# msq_ethrottle_soic.net
KiCad netlist of a schematic drawn in EasyEDA Pro
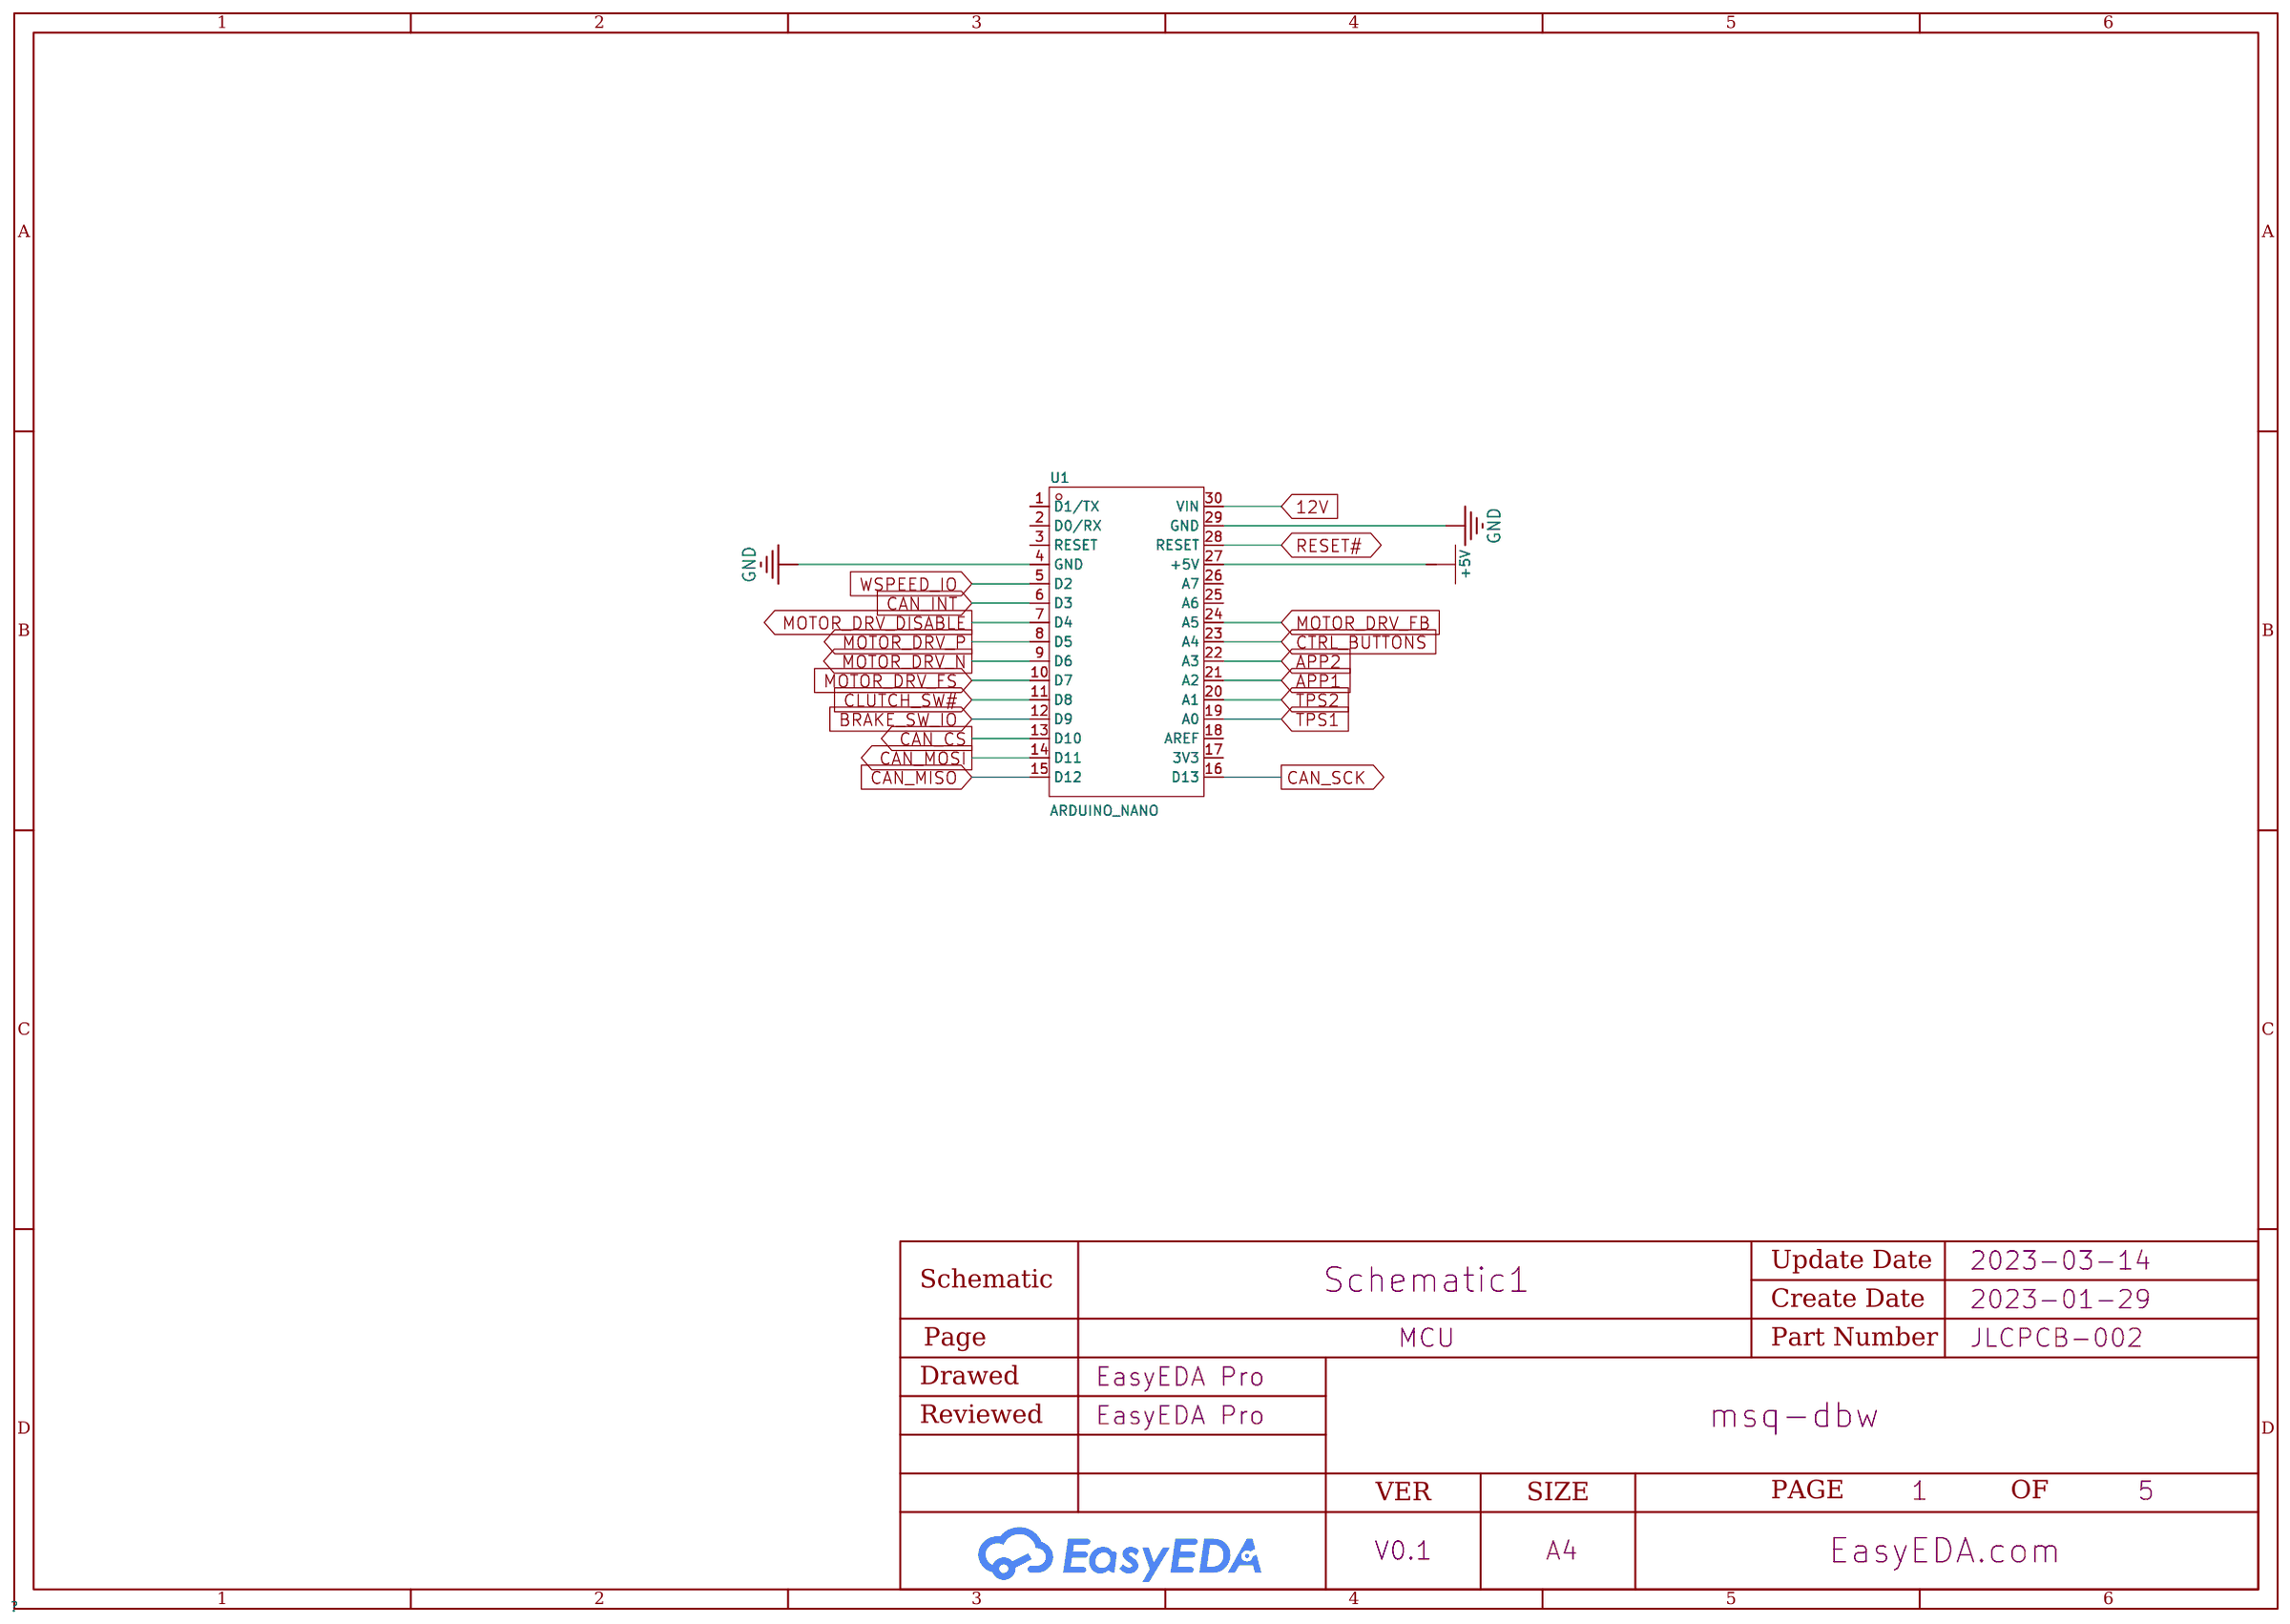
[diagram p0: MCU]
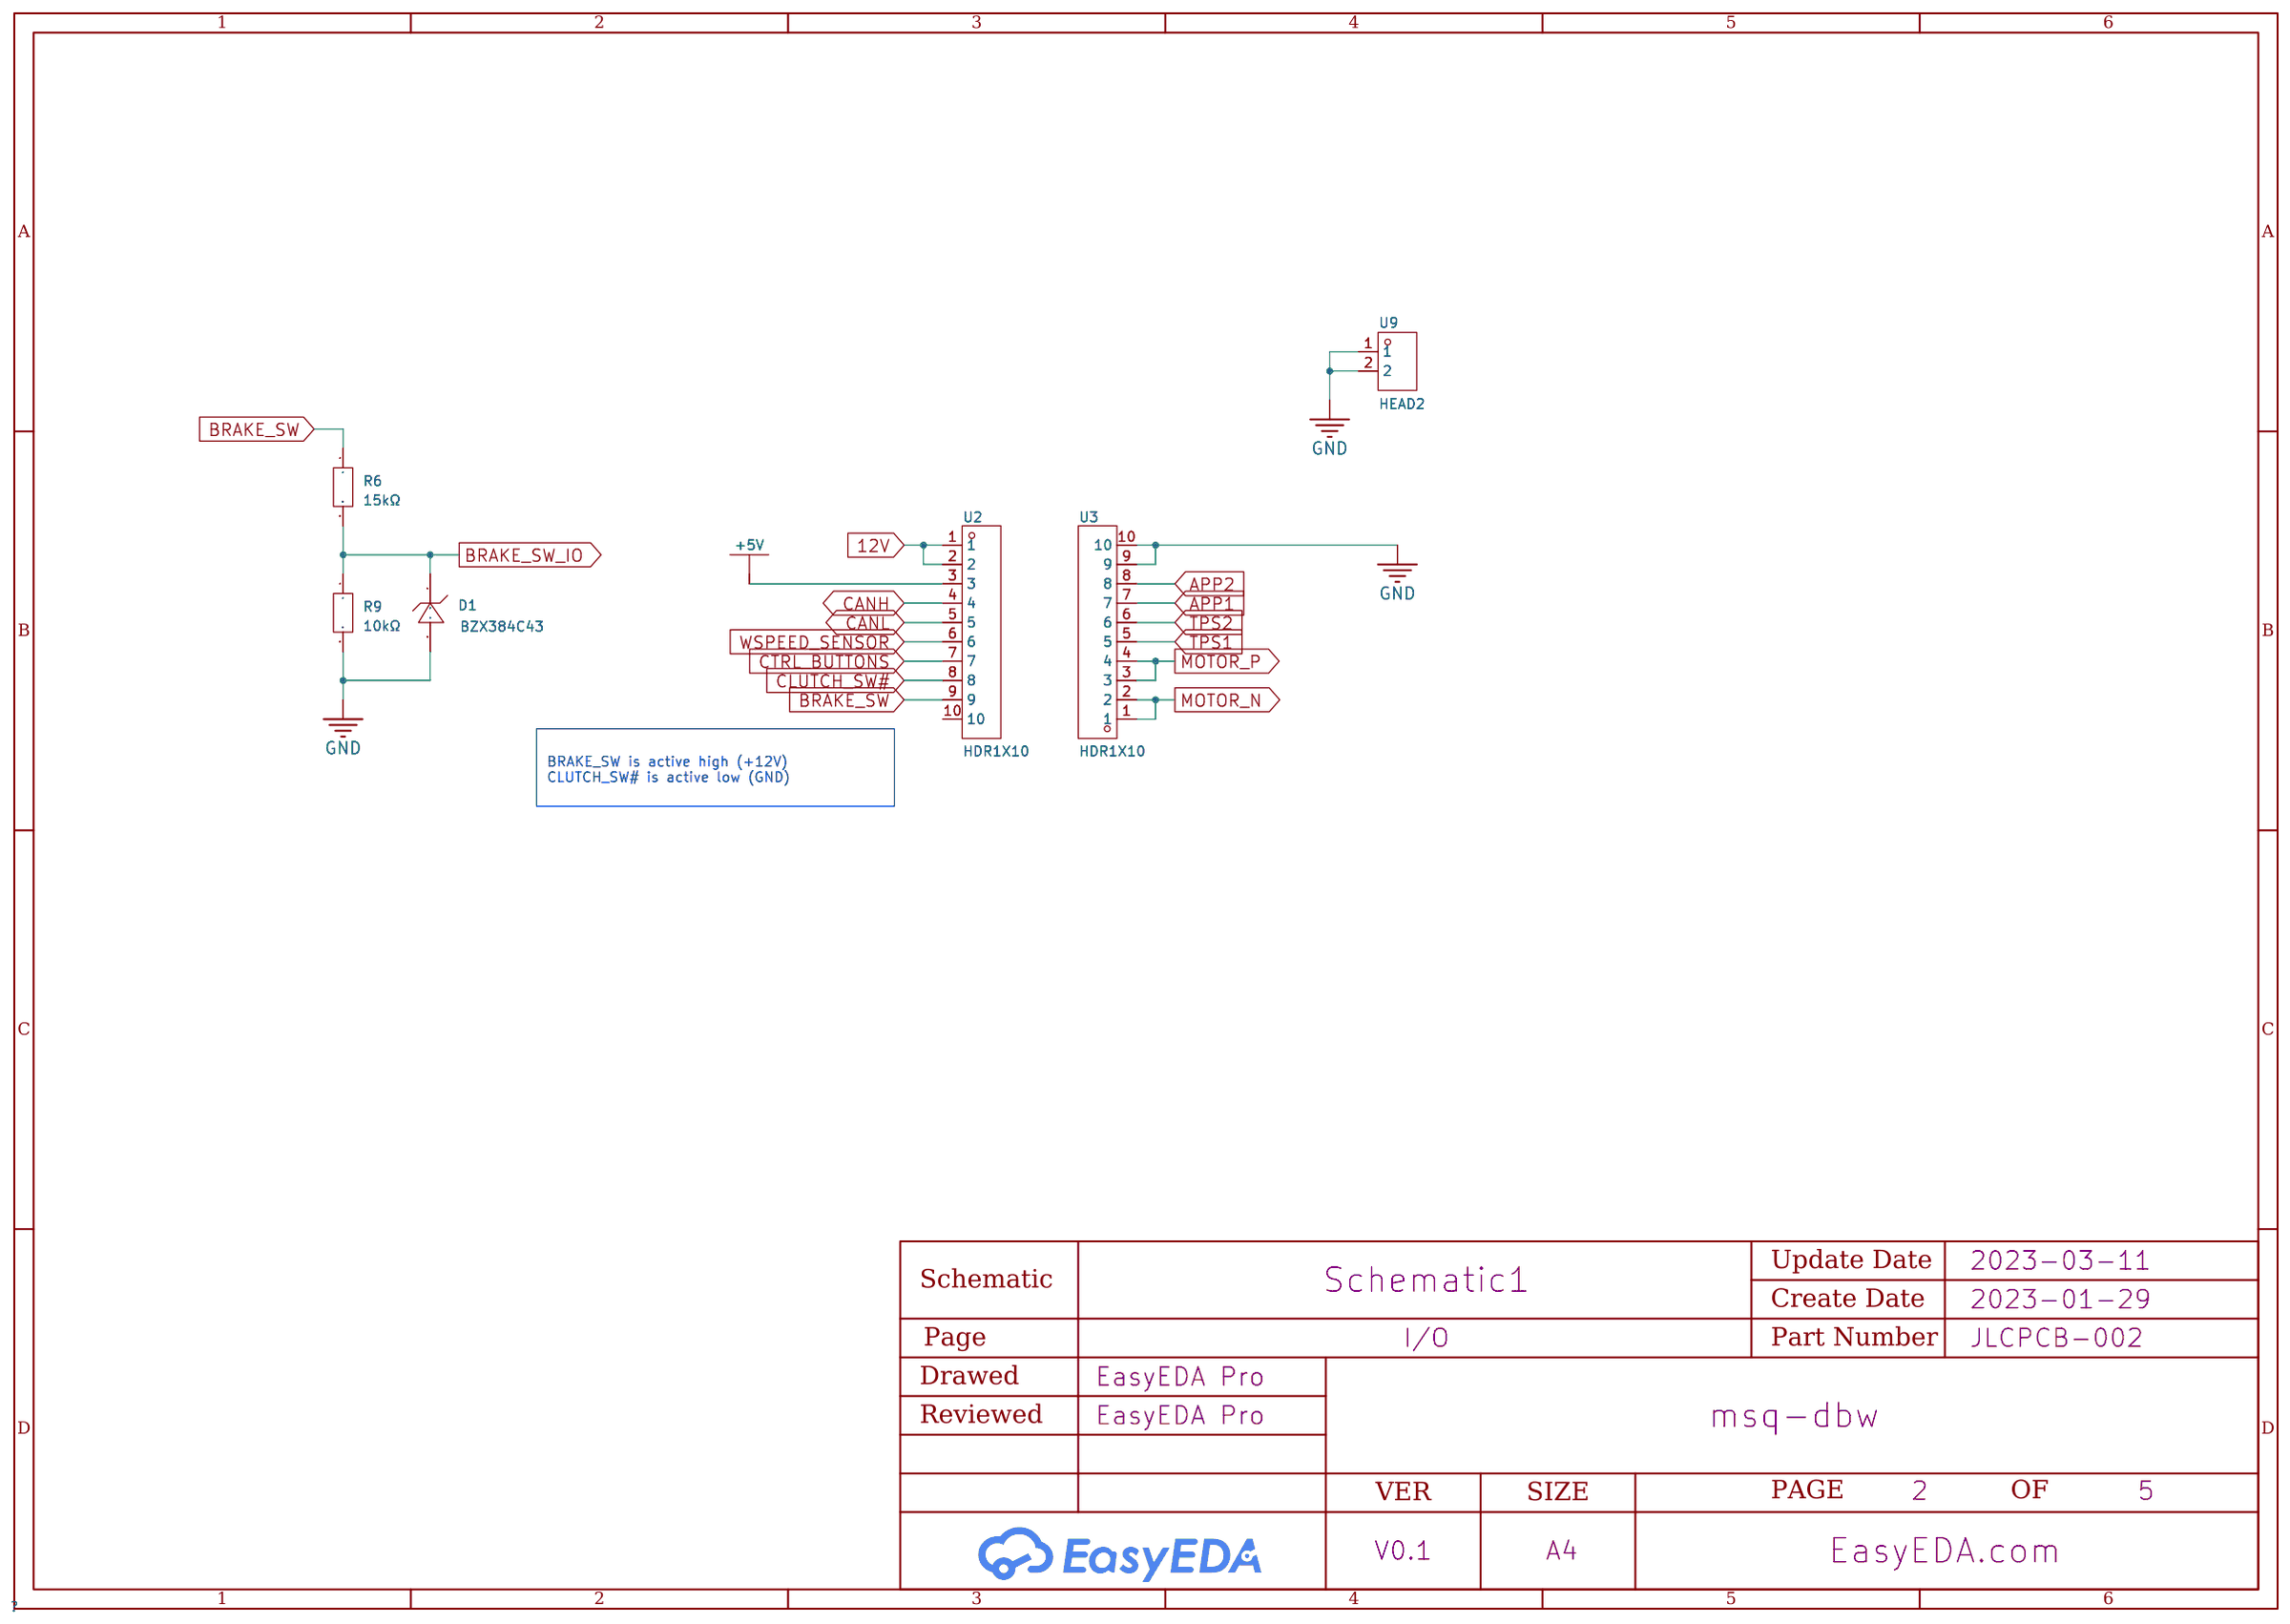
[diagram p1: I/O]
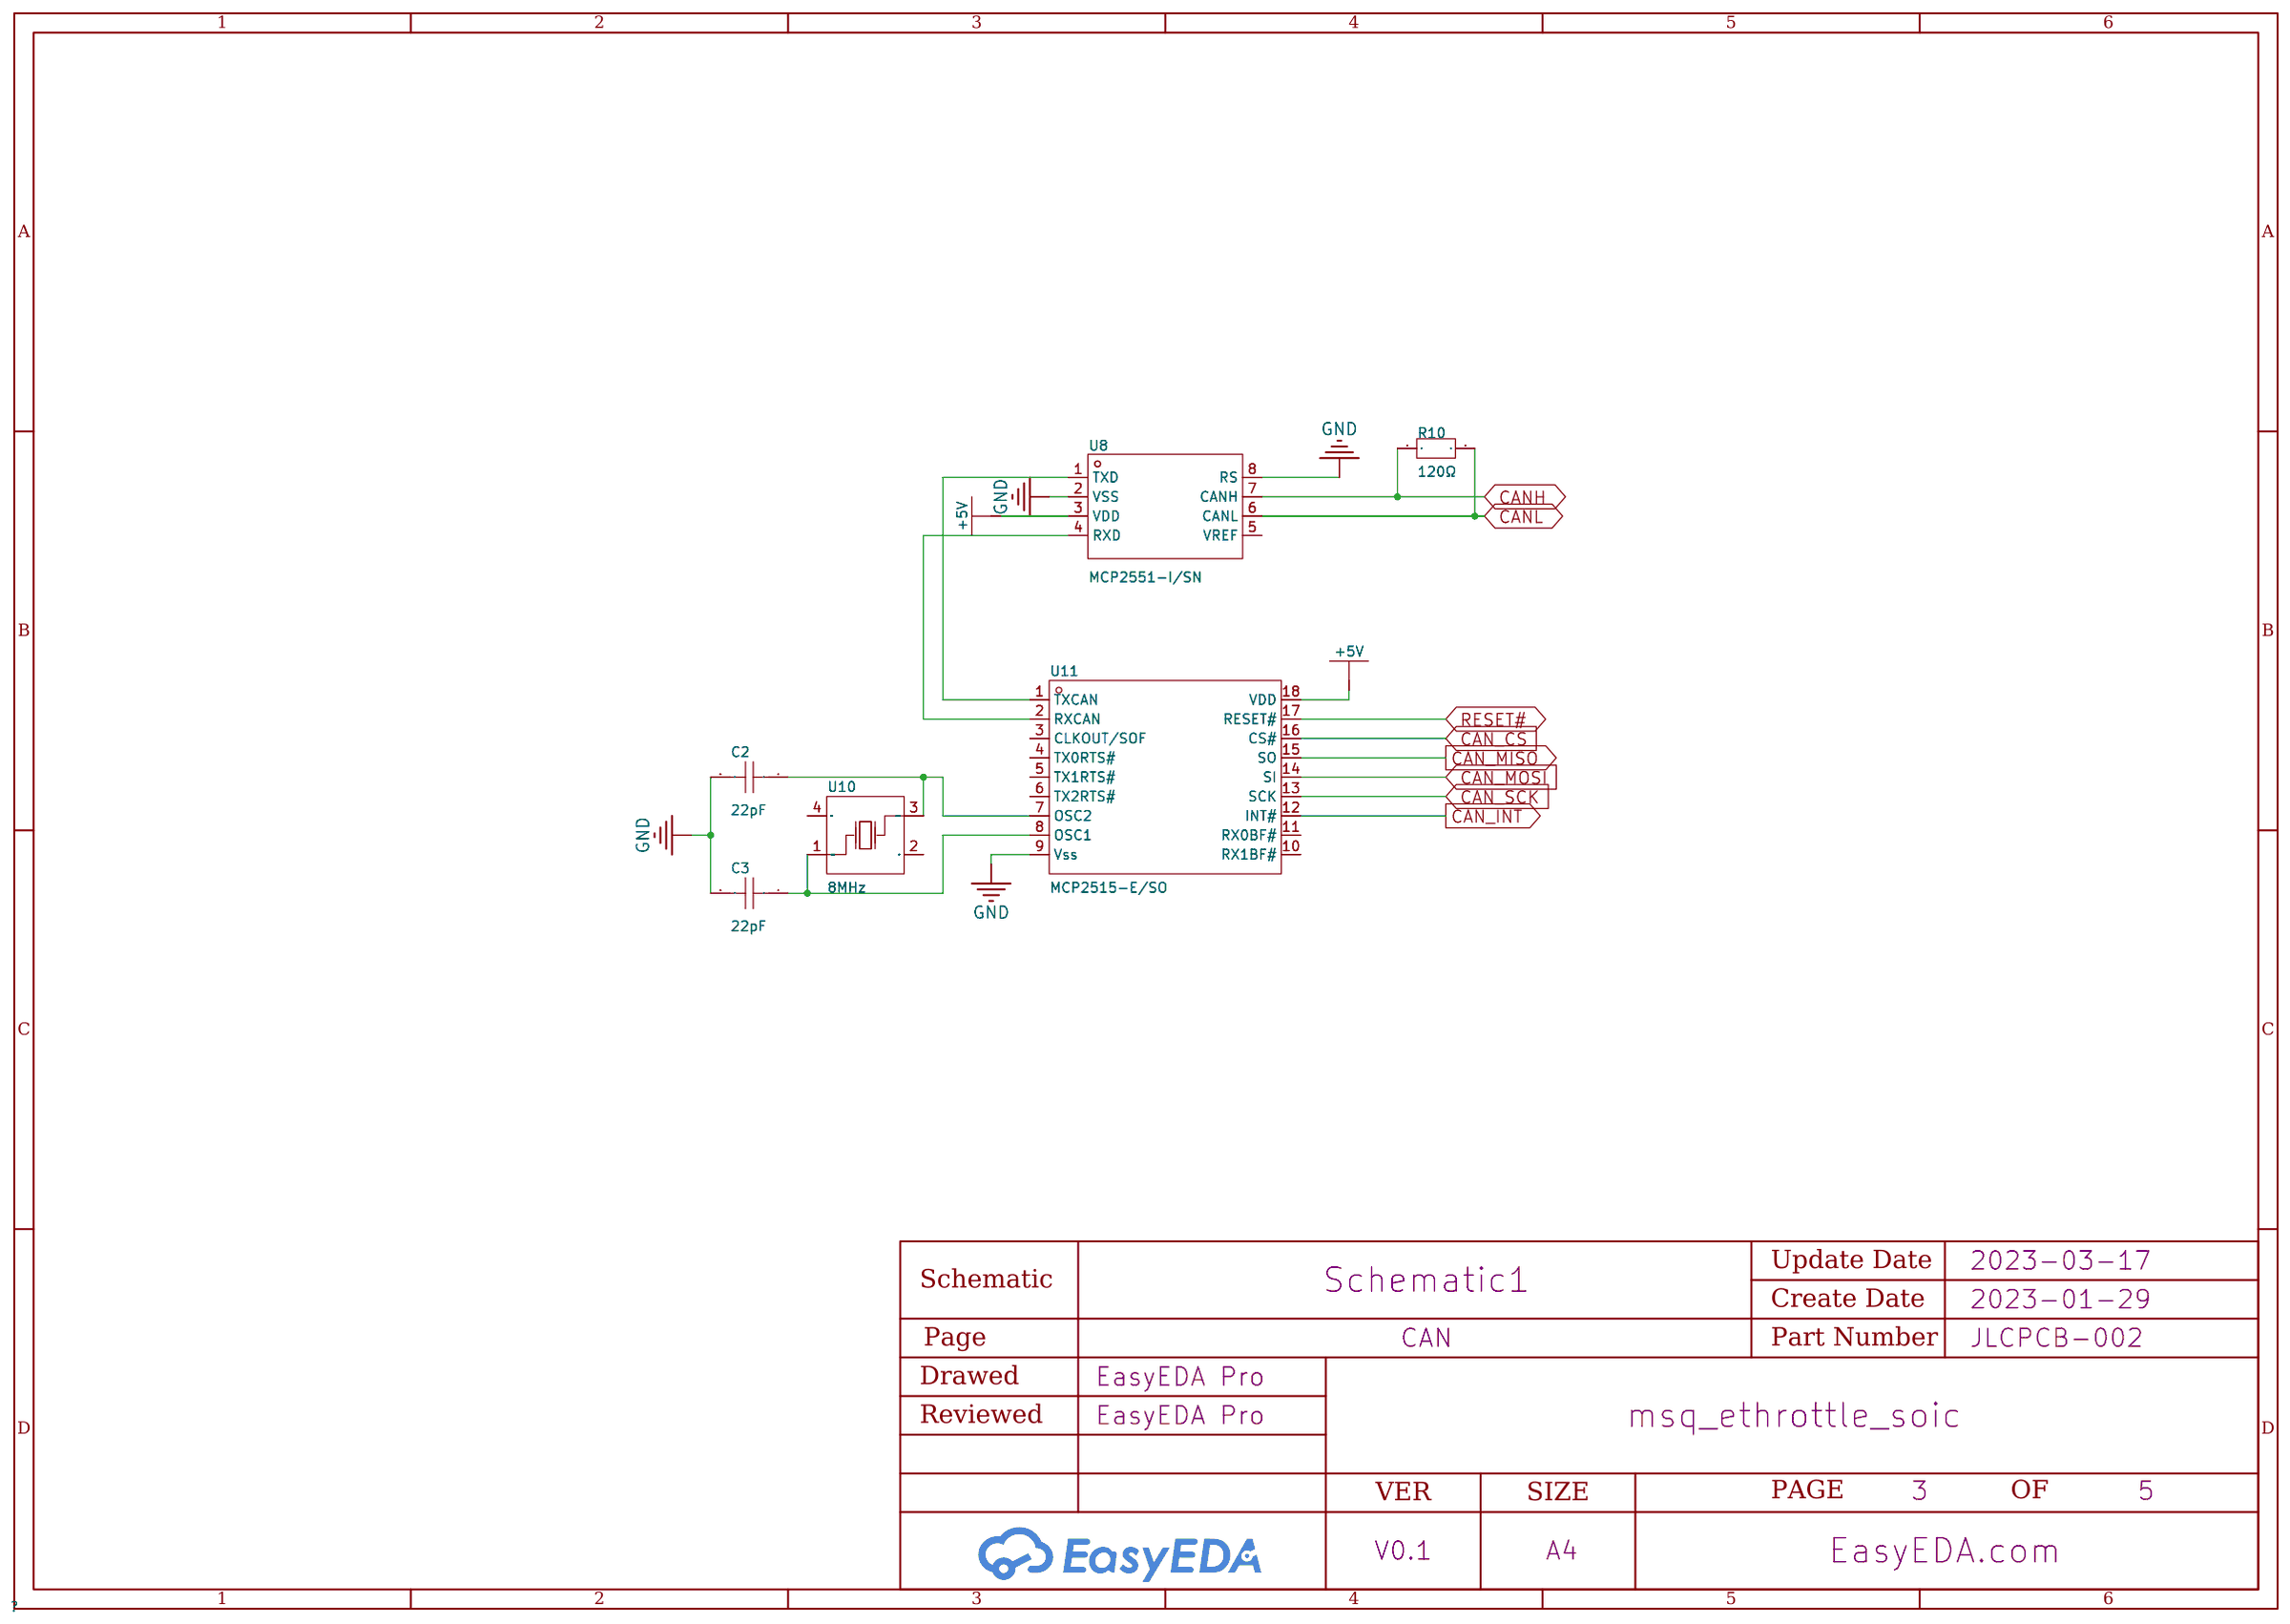
[diagram p2: CAN]
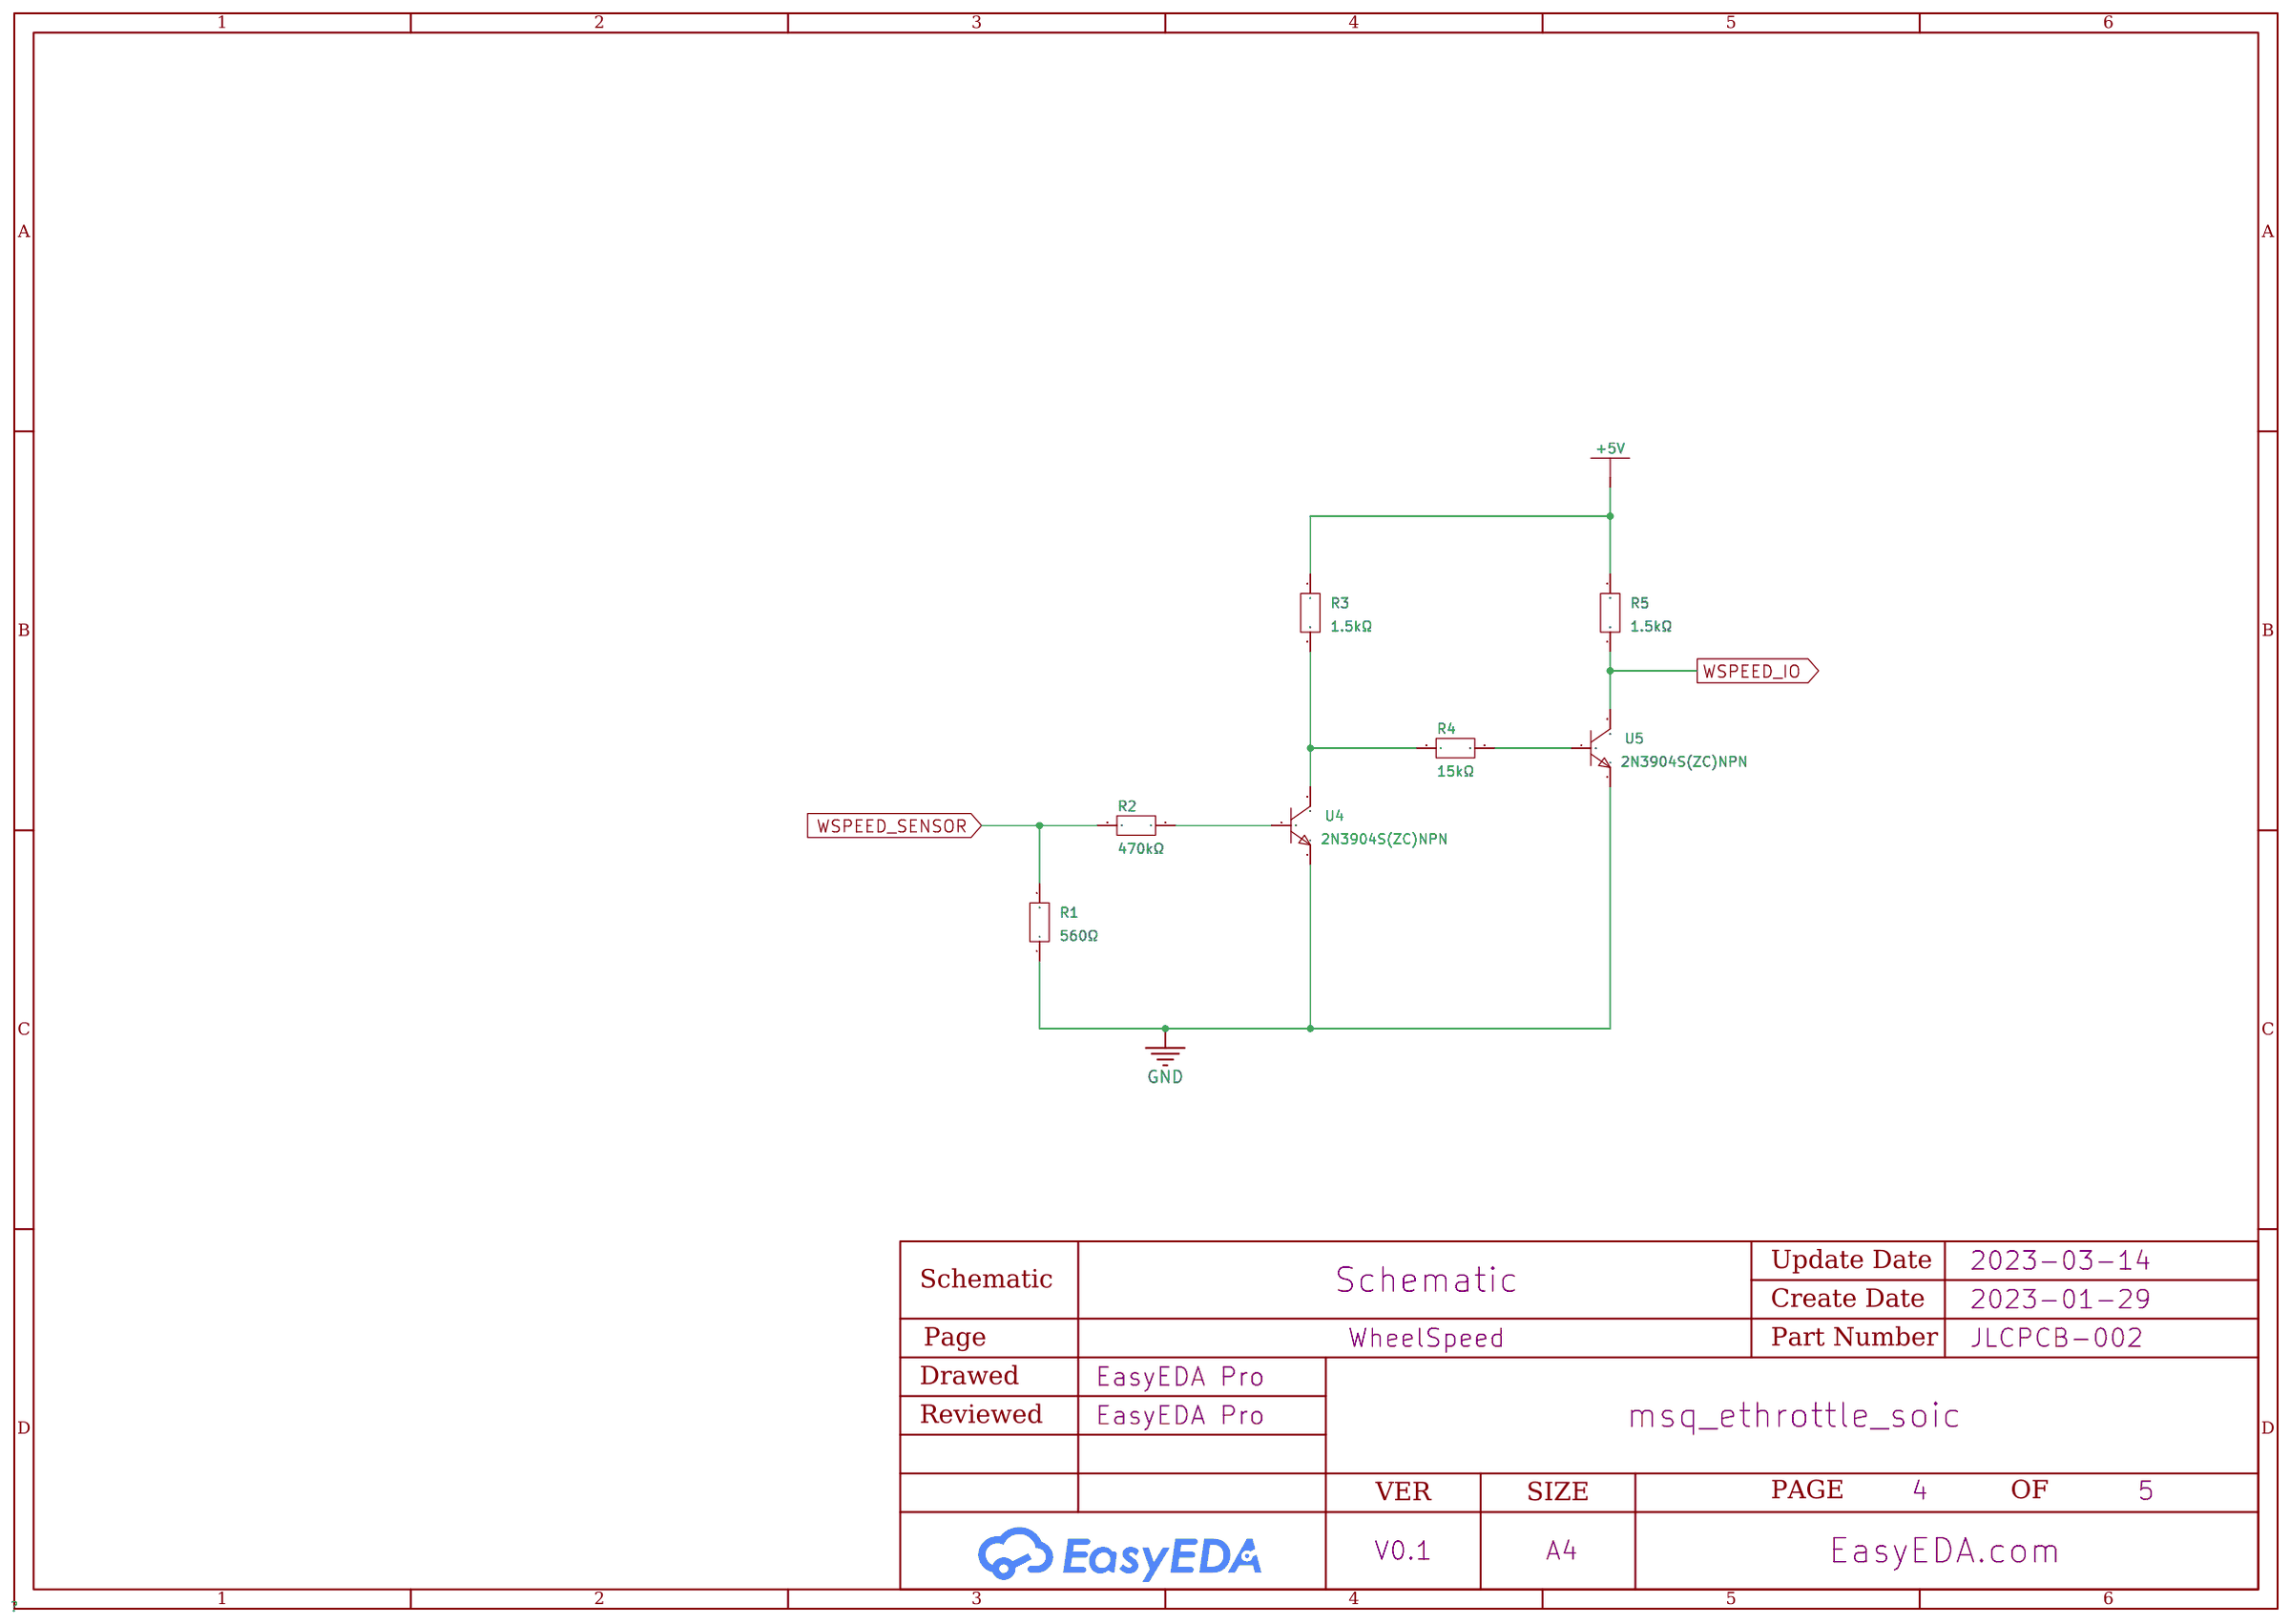
[diagram p3: WheelSpeed]
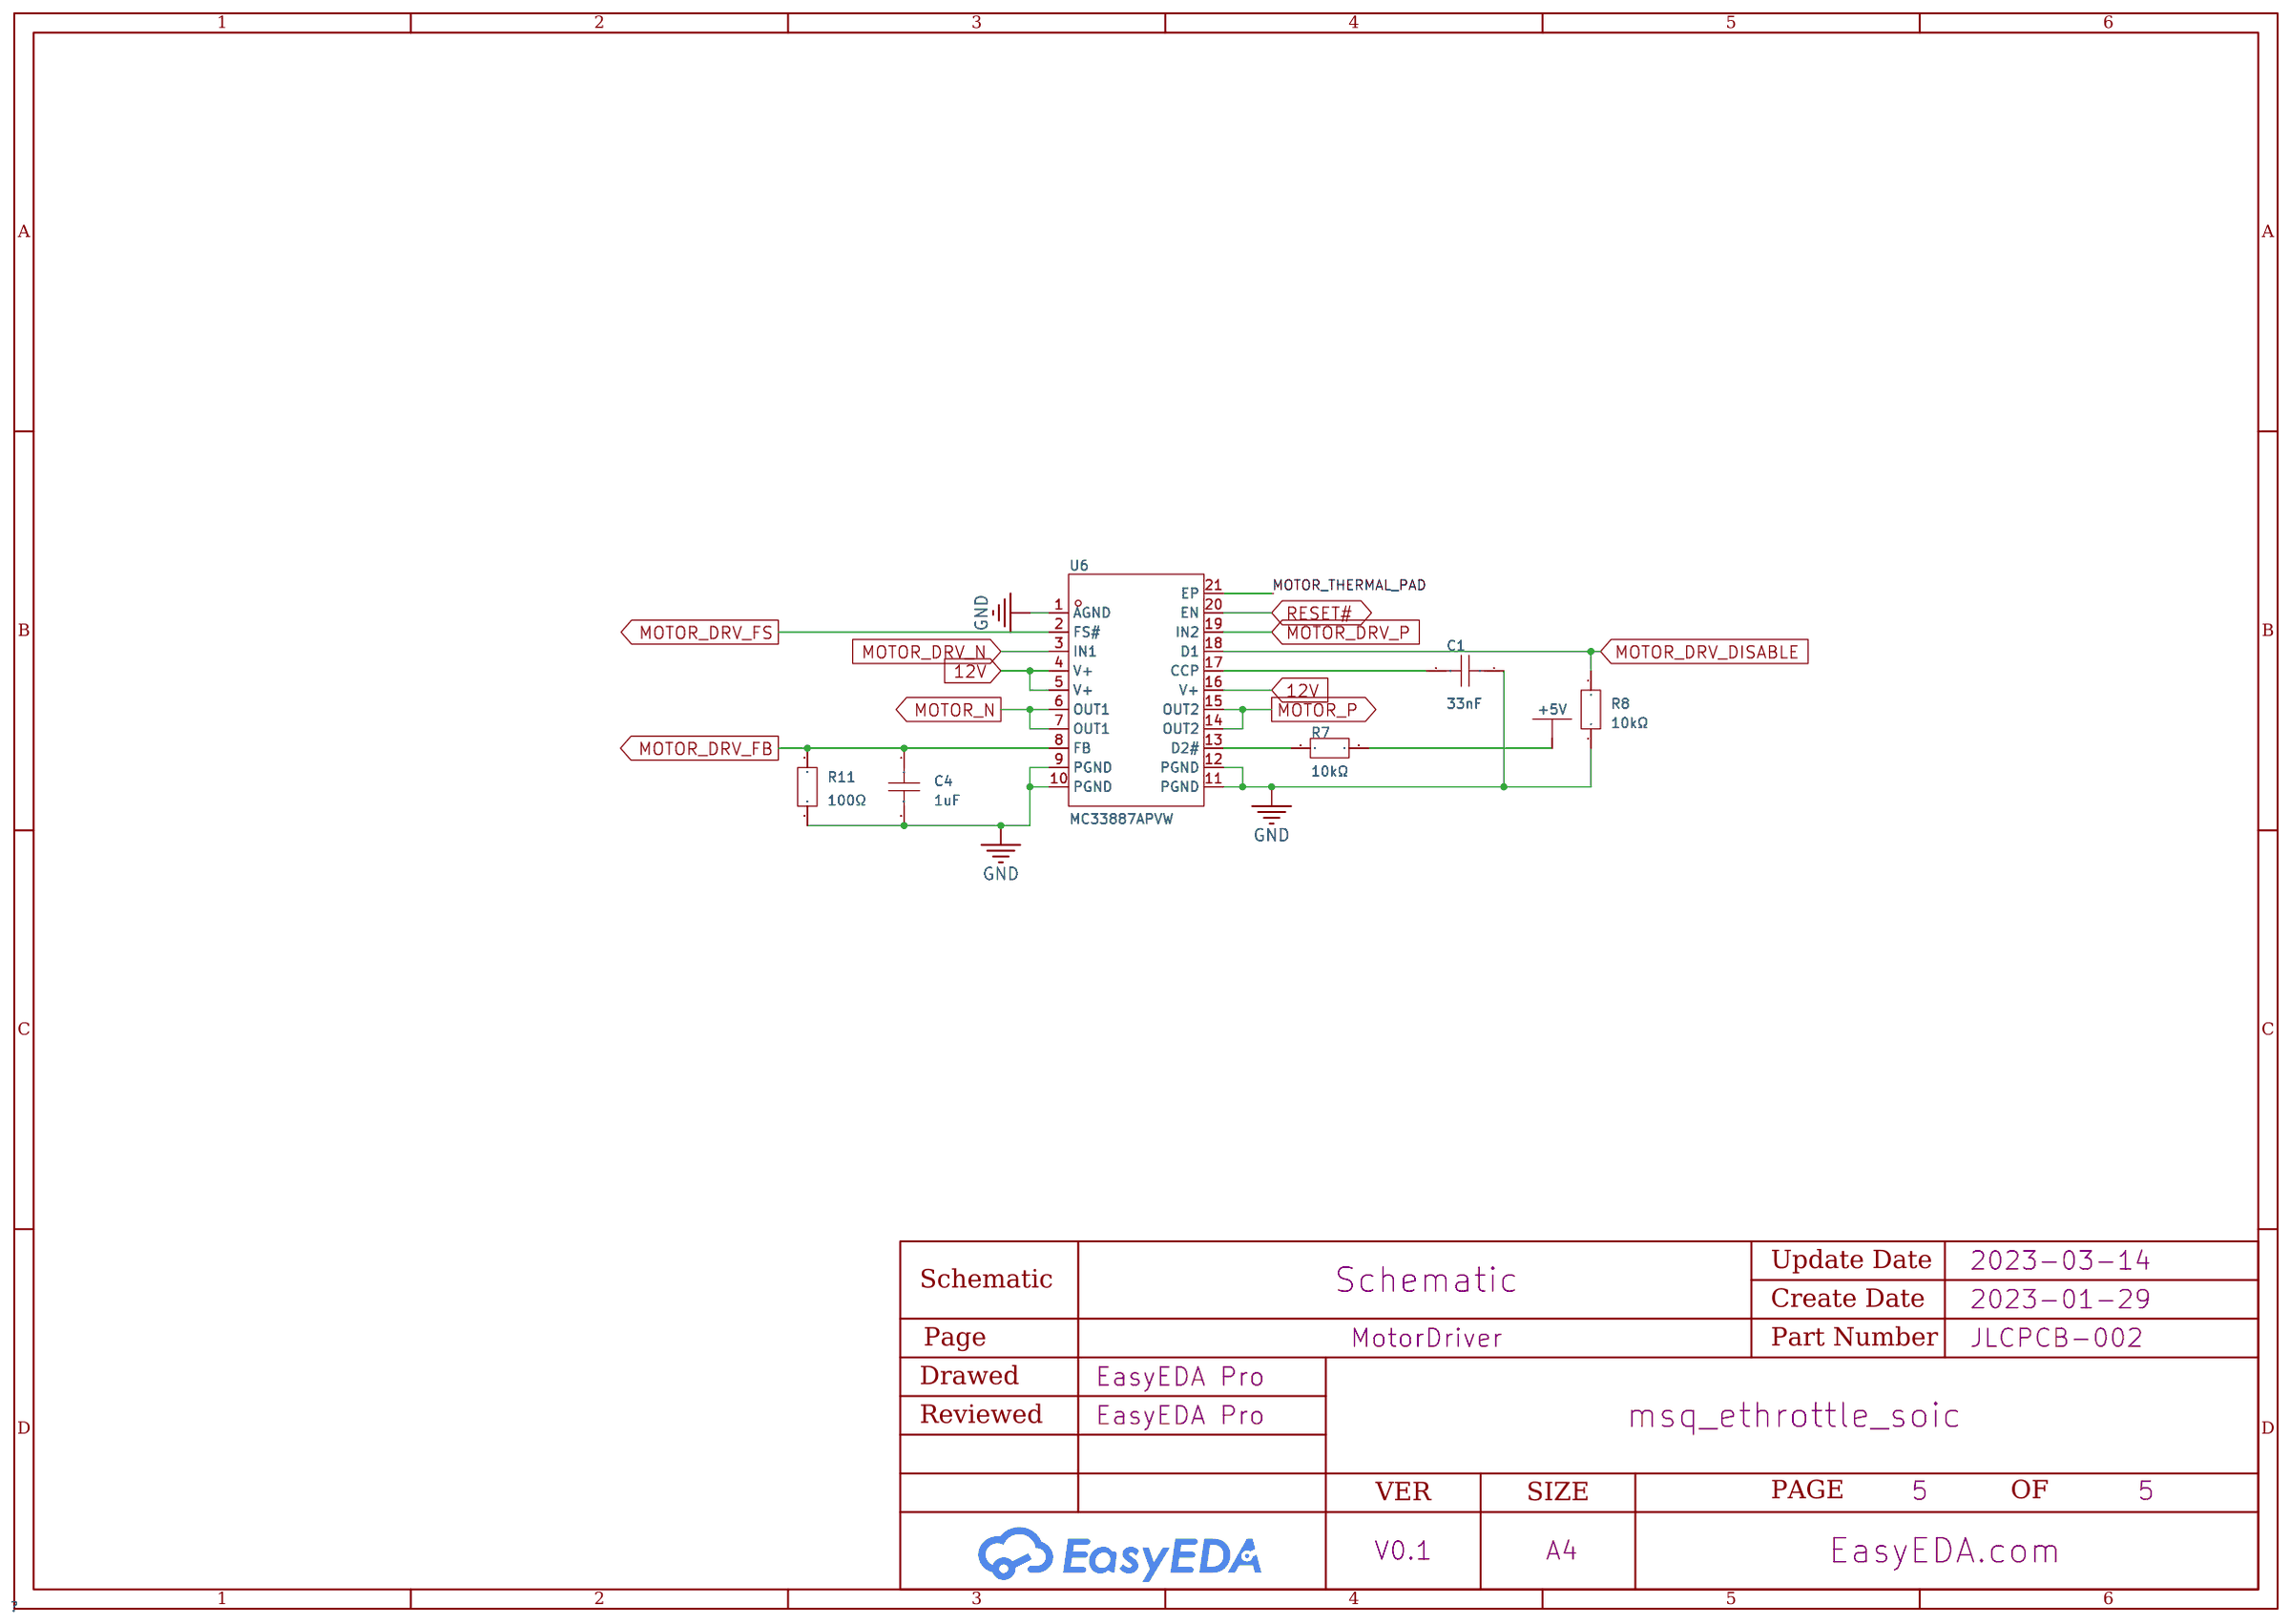
[diagram p4: MotorDriver]

(export (version "E")
  (design (tool "Eeschema 10.0.6"))
  (components
    (comp (ref "U1")
      (value "ARDUINO_NANO")
      (footprint "easyedapro:COMM-TH_ARDUINO_NANO")
      (libsource (lib "easyedapro") (part "ARDUINO_NANO"))
    )
    (comp (ref "D1")
      (value "BZX384C43")
      (footprint "easyedapro:SOD-323_L1.7-W1.3-LS2.6-RD")
      (fields (field (name "Manufacturer") "EIC") (field (name "Tolerance") "±2%"))
      (libsource (lib "easyedapro") (part "BZX384C43"))
    )
    (comp (ref "R6")
      (value "15kΩ")
      (footprint "easyedapro:R0805")
      (fields
        (field (name "Manufacturer Part") "0603WAF1002T5E")
        (field (name "Manufacturer") "UNI-ROYAL(厚声)")
        (field (name "Tolerance") "±1%")
      )
      (libsource (lib "easyedapro") (part "RT0805BRD07360RL"))
    )
    (comp (ref "R9")
      (value "10kΩ")
      (footprint "easyedapro:R0805")
      (fields
        (field (name "Manufacturer Part") "0603WAF1002T5E")
        (field (name "Manufacturer") "UNI-ROYAL(厚声)")
        (field (name "Tolerance") "±1%")
      )
      (libsource (lib "easyedapro") (part "RT0805BRD07360RL"))
    )
    (comp (ref "U2")
      (value "HDR1X10")
      (footprint "easyedapro:HDR-TH_10P-P2.54-V-F_C9900008052")
      (libsource (lib "easyedapro") (part "HDR1X10"))
    )
    (comp (ref "U3")
      (value "HDR1X10")
      (footprint "easyedapro:HDR-TH_10P-P2.54-V-F_C9900008052")
      (libsource (lib "easyedapro") (part "HDR1X10"))
    )
    (comp (ref "U9")
      (value "HEAD2")
      (footprint "easyedapro:HDR-TH_2P-P2.54-V-M")
      (libsource (lib "easyedapro") (part "HEAD2"))
    )
    (comp (ref "C2")
      (value "22pF")
      (footprint "easyedapro:C0603")
      (libsource (lib "easyedapro") (part "CAP"))
    )
    (comp (ref "C3")
      (value "22pF")
      (footprint "easyedapro:C0603")
      (libsource (lib "easyedapro") (part "CAP"))
    )
    (comp (ref "R10")
      (value "120Ω")
      (footprint "easyedapro:R0805")
      (fields
        (field (name "Manufacturer Part") "0603WAF1002T5E")
        (field (name "Manufacturer") "UNI-ROYAL(厚声)")
        (field (name "Tolerance") "±1%")
      )
      (libsource (lib "easyedapro") (part "RT0805BRD07360RL"))
    )
    (comp (ref "U8")
      (value "MCP2551-I/SN")
      (footprint "easyedapro:SOIC-8_L4.9-W3.9-P1.27-LS6.0-BL")
      (description "Type:Transceiver Supply Voltage:4.5V~5.5V Supply Voltage:4.5V~5.5V")
      (fields (field (name "Manufacturer") "MICROCHIP(美国微芯)"))
      (libsource (lib "easyedapro") (part "MCP2551-I/SN"))
    )
    (comp (ref "U10")
      (value "8MHz")
      (footprint "easyedapro:CRYSTAL-SMD_4P-L3.2-W2.5-BL")
      (fields (field (name "Manufacturer Part") "L327S270S11L") (field (name "Manufacturer") "Lucki(蓝晶)"))
      (libsource (lib "easyedapro") (part "L327S270S11L"))
    )
    (comp (ref "U11")
      (value "MCP2515-E/SO")
      (footprint "easyedapro:SOIC-18_L11.6-W7.5-P1.27-LS10.3-BL")
      (fields (field (name "Manufacturer") "MICROCHIP(美国微芯)"))
      (libsource (lib "easyedapro") (part "MCP2515-E/SO"))
    )
    (comp (ref "R1")
      (value "560Ω")
      (footprint "easyedapro:R0805")
      (fields
        (field (name "Manufacturer Part") "0603WAF1002T5E")
        (field (name "Manufacturer") "UNI-ROYAL(厚声)")
        (field (name "Tolerance") "±1%")
      )
      (libsource (lib "easyedapro") (part "RT0805BRD07360RL"))
    )
    (comp (ref "R2")
      (value "470kΩ")
      (footprint "easyedapro:R0805")
      (fields
        (field (name "Manufacturer Part") "0603WAF1002T5E")
        (field (name "Manufacturer") "UNI-ROYAL(厚声)")
        (field (name "Tolerance") "±1%")
      )
      (libsource (lib "easyedapro") (part "RT0805BRD07360RL"))
    )
    (comp (ref "R3")
      (value "1.5kΩ")
      (footprint "easyedapro:R0805")
      (fields
        (field (name "Manufacturer Part") "0603WAF1002T5E")
        (field (name "Manufacturer") "UNI-ROYAL(厚声)")
        (field (name "Tolerance") "±1%")
      )
      (libsource (lib "easyedapro") (part "RT0805BRD07360RL"))
    )
    (comp (ref "R4")
      (value "15kΩ")
      (footprint "easyedapro:R0805")
      (fields
        (field (name "Manufacturer Part") "0603WAF1002T5E")
        (field (name "Manufacturer") "UNI-ROYAL(厚声)")
        (field (name "Tolerance") "±1%")
      )
      (libsource (lib "easyedapro") (part "RT0805BRD07360RL"))
    )
    (comp (ref "R5")
      (value "1.5kΩ")
      (footprint "easyedapro:R0805")
      (fields
        (field (name "Manufacturer Part") "0603WAF1002T5E")
        (field (name "Manufacturer") "UNI-ROYAL(厚声)")
        (field (name "Tolerance") "±1%")
      )
      (libsource (lib "easyedapro") (part "RT0805BRD07360RL"))
    )
    (comp (ref "U4")
      (value "2N3904S(ZC)NPN")
      (footprint "easyedapro:SOT-23-3_L2.9-W1.3-P0.95-LS2.4-BR")
      (libsource (lib "easyedapro") (part "2N3904S(ZC)NPN"))
    )
    (comp (ref "U5")
      (value "2N3904S(ZC)NPN")
      (footprint "easyedapro:SOT-23-3_L2.9-W1.3-P0.95-LS2.4-BR")
      (libsource (lib "easyedapro") (part "2N3904S(ZC)NPN"))
    )
    (comp (ref "C1")
      (value "33nF")
      (footprint "easyedapro:C0603")
      (libsource (lib "easyedapro") (part "CAP"))
    )
    (comp (ref "C4") (value "1uF") (footprint "easyedapro:C0603") (libsource (lib "easyedapro") (part "CAP")))
    (comp (ref "R7")
      (value "10kΩ")
      (footprint "easyedapro:R0805")
      (fields
        (field (name "Manufacturer Part") "0603WAF1002T5E")
        (field (name "Manufacturer") "UNI-ROYAL(厚声)")
        (field (name "Tolerance") "±1%")
      )
      (libsource (lib "easyedapro") (part "RT0805BRD07360RL"))
    )
    (comp (ref "R8")
      (value "10kΩ")
      (footprint "easyedapro:R0805")
      (fields
        (field (name "Manufacturer Part") "0603WAF1002T5E")
        (field (name "Manufacturer") "UNI-ROYAL(厚声)")
        (field (name "Tolerance") "±1%")
      )
      (libsource (lib "easyedapro") (part "RT0805BRD07360RL"))
    )
    (comp (ref "R11")
      (value "100Ω")
      (footprint "easyedapro:R0805")
      (fields
        (field (name "Manufacturer Part") "0603WAF1002T5E")
        (field (name "Manufacturer") "UNI-ROYAL(厚声)")
        (field (name "Tolerance") "±1%")
      )
      (libsource (lib "easyedapro") (part "RT0805BRD07360RL"))
    )
    (comp (ref "U6")
      (value "MC33887APVW")
      (footprint "easyedapro:HSOP-20_L15.9-W11.0-P1.27-LS14.2-TL-EP")
      (fields (field (name "Manufacturer") "NXP(恩智浦)"))
      (libsource (lib "easyedapro") (part "MC33887APVW"))
    )
  )
  (nets
    (net (code "1") (name "+5V") (class "Default")
      (node (ref "R3") (pin "1") (pinfunction "1_1") (pintype "input"))
      (node (ref "R5") (pin "2") (pinfunction "2_2") (pintype "input"))
      (node (ref "R7") (pin "1") (pinfunction "1_1") (pintype "input"))
      (node (ref "U1") (pin "27") (pinfunction "+5V_27") (pintype "input"))
      (node (ref "U11") (pin "18") (pinfunction "VDD_18") (pintype "input"))
      (node (ref "U2") (pin "3") (pinfunction "3_3") (pintype "input"))
      (node (ref "U8") (pin "3") (pinfunction "VDD_3") (pintype "input"))
    )
    (net (code "2") (name "12V") (class "Default")
      (node (ref "U1") (pin "30") (pinfunction "VIN_30") (pintype "input"))
      (node (ref "U2") (pin "1") (pinfunction "1_1") (pintype "input"))
      (node (ref "U2") (pin "2") (pinfunction "2_2") (pintype "input"))
      (node (ref "U6") (pin "16") (pinfunction "V+_16") (pintype "input"))
      (node (ref "U6") (pin "4") (pinfunction "V+_4") (pintype "input"))
      (node (ref "U6") (pin "5") (pinfunction "V+_5") (pintype "input"))
    )
    (net (code "3") (name "APP1") (class "Default")
      (node (ref "U1") (pin "21") (pinfunction "A2_21") (pintype "input"))
      (node (ref "U3") (pin "7") (pinfunction "7_7") (pintype "input"))
    )
    (net (code "4") (name "APP2") (class "Default")
      (node (ref "U1") (pin "22") (pinfunction "A3_22") (pintype "input"))
      (node (ref "U3") (pin "8") (pinfunction "8_8") (pintype "input"))
    )
    (net (code "5") (name "BRAKE_SW") (class "Default")
      (node (ref "R6") (pin "1") (pinfunction "1_1") (pintype "input"))
      (node (ref "U2") (pin "9") (pinfunction "9_9") (pintype "input"))
    )
    (net (code "6") (name "BRAKE_SW_IO") (class "Default")
      (node (ref "D1") (pin "1") (pinfunction "C_1") (pintype "input"))
      (node (ref "R6") (pin "2") (pinfunction "2_2") (pintype "input"))
      (node (ref "R9") (pin "1") (pinfunction "1_1") (pintype "input"))
      (node (ref "U1") (pin "12") (pinfunction "D9_12") (pintype "input"))
    )
    (net (code "7") (name "CANH") (class "Default")
      (node (ref "R10") (pin "1") (pinfunction "1_1") (pintype "input"))
      (node (ref "U2") (pin "4") (pinfunction "4_4") (pintype "input"))
      (node (ref "U8") (pin "7") (pinfunction "CANH_7") (pintype "input"))
    )
    (net (code "8") (name "CANL") (class "Default")
      (node (ref "R10") (pin "2") (pinfunction "2_2") (pintype "input"))
      (node (ref "U2") (pin "5") (pinfunction "5_5") (pintype "input"))
      (node (ref "U8") (pin "6") (pinfunction "CANL_6") (pintype "input"))
    )
    (net (code "9") (name "CAN_CS") (class "Default")
      (node (ref "U1") (pin "13") (pinfunction "D10_13") (pintype "input"))
      (node (ref "U11") (pin "16") (pinfunction "CS#_16") (pintype "input"))
    )
    (net (code "10") (name "CAN_INT") (class "Default")
      (node (ref "U1") (pin "6") (pinfunction "D3_6") (pintype "input"))
      (node (ref "U11") (pin "12") (pinfunction "INT#_12") (pintype "input"))
    )
    (net (code "11") (name "CAN_MISO") (class "Default")
      (node (ref "U1") (pin "15") (pinfunction "D12_15") (pintype "input"))
      (node (ref "U11") (pin "15") (pinfunction "SO_15") (pintype "input"))
    )
    (net (code "12") (name "CAN_MOSI") (class "Default")
      (node (ref "U1") (pin "14") (pinfunction "D11_14") (pintype "input"))
      (node (ref "U11") (pin "14") (pinfunction "SI_14") (pintype "input"))
    )
    (net (code "13") (name "CAN_SCK") (class "Default")
      (node (ref "U1") (pin "16") (pinfunction "D13_16") (pintype "input"))
      (node (ref "U11") (pin "13") (pinfunction "SCK_13") (pintype "input"))
    )
    (net (code "14") (name "CLUTCH_SW#") (class "Default")
      (node (ref "U1") (pin "11") (pinfunction "D8_11") (pintype "input"))
      (node (ref "U2") (pin "8") (pinfunction "8_8") (pintype "input"))
    )
    (net (code "15") (name "CTRL_BUTTONS") (class "Default")
      (node (ref "U1") (pin "23") (pinfunction "A4_23") (pintype "input"))
      (node (ref "U2") (pin "7") (pinfunction "7_7") (pintype "input"))
    )
    (net (code "16") (name "GND") (class "Default")
      (node (ref "C1") (pin "1") (pinfunction "1_1") (pintype "input"))
      (node (ref "C2") (pin "2") (pinfunction "2_2") (pintype "input"))
      (node (ref "C3") (pin "2") (pinfunction "2_2") (pintype "input"))
      (node (ref "C4") (pin "2") (pinfunction "2_2") (pintype "input"))
      (node (ref "D1") (pin "2") (pinfunction "A_2") (pintype "input"))
      (node (ref "R1") (pin "1") (pinfunction "1_1") (pintype "input"))
      (node (ref "R11") (pin "1") (pinfunction "1_1") (pintype "input"))
      (node (ref "R8") (pin "2") (pinfunction "2_2") (pintype "input"))
      (node (ref "R9") (pin "2") (pinfunction "2_2") (pintype "input"))
      (node (ref "U1") (pin "29") (pinfunction "GND_29") (pintype "input"))
      (node (ref "U1") (pin "4") (pinfunction "GND_4") (pintype "input"))
      (node (ref "U11") (pin "9") (pinfunction "Vss_9") (pintype "input"))
      (node (ref "U3") (pin "10") (pinfunction "10_10") (pintype "input"))
      (node (ref "U3") (pin "9") (pinfunction "9_9") (pintype "input"))
      (node (ref "U4") (pin "2") (pinfunction "E_2") (pintype "input"))
      (node (ref "U5") (pin "2") (pinfunction "E_2") (pintype "input"))
      (node (ref "U6") (pin "1") (pinfunction "AGND_1") (pintype "input"))
      (node (ref "U6") (pin "10") (pinfunction "PGND_10") (pintype "input"))
      (node (ref "U6") (pin "11") (pinfunction "PGND_11") (pintype "input"))
      (node (ref "U6") (pin "12") (pinfunction "PGND_12") (pintype "input"))
      (node (ref "U6") (pin "9") (pinfunction "PGND_9") (pintype "input"))
      (node (ref "U8") (pin "2") (pinfunction "VSS_2") (pintype "input"))
      (node (ref "U8") (pin "8") (pinfunction "RS_8") (pintype "input"))
      (node (ref "U9") (pin "1") (pinfunction "1_1") (pintype "input"))
      (node (ref "U9") (pin "2") (pinfunction "2_2") (pintype "input"))
    )
    (net (code "17") (name "MOTOR_DRV_DISABLE") (class "Default")
      (node (ref "R8") (pin "1") (pinfunction "1_1") (pintype "input"))
      (node (ref "U1") (pin "7") (pinfunction "D4_7") (pintype "input"))
      (node (ref "U6") (pin "18") (pinfunction "D1_18") (pintype "input"))
    )
    (net (code "18") (name "MOTOR_DRV_FB") (class "Default")
      (node (ref "C4") (pin "1") (pinfunction "1_1") (pintype "input"))
      (node (ref "R11") (pin "2") (pinfunction "2_2") (pintype "input"))
      (node (ref "U1") (pin "24") (pinfunction "A5_24") (pintype "input"))
      (node (ref "U6") (pin "8") (pinfunction "FB_8") (pintype "input"))
    )
    (net (code "19") (name "MOTOR_DRV_FS") (class "Default")
      (node (ref "U1") (pin "10") (pinfunction "D7_10") (pintype "input"))
      (node (ref "U6") (pin "2") (pinfunction "FS#_2") (pintype "input"))
    )
    (net (code "20") (name "MOTOR_DRV_N") (class "Default")
      (node (ref "U1") (pin "9") (pinfunction "D6_9") (pintype "input"))
      (node (ref "U6") (pin "3") (pinfunction "IN1_3") (pintype "input"))
    )
    (net (code "21") (name "MOTOR_DRV_P") (class "Default")
      (node (ref "U1") (pin "8") (pinfunction "D5_8") (pintype "input"))
      (node (ref "U6") (pin "19") (pinfunction "IN2_19") (pintype "input"))
    )
    (net (code "22") (name "MOTOR_N") (class "Default")
      (node (ref "U3") (pin "1") (pinfunction "1_1") (pintype "input"))
      (node (ref "U3") (pin "2") (pinfunction "2_2") (pintype "input"))
      (node (ref "U6") (pin "6") (pinfunction "OUT1_6") (pintype "input"))
      (node (ref "U6") (pin "7") (pinfunction "OUT1_7") (pintype "input"))
    )
    (net (code "23") (name "MOTOR_P") (class "Default")
      (node (ref "U3") (pin "3") (pinfunction "3_3") (pintype "input"))
      (node (ref "U3") (pin "4") (pinfunction "4_4") (pintype "input"))
      (node (ref "U6") (pin "14") (pinfunction "OUT2_14") (pintype "input"))
      (node (ref "U6") (pin "15") (pinfunction "OUT2_15") (pintype "input"))
    )
    (net (code "24") (name "MOTOR_THERMAL_PAD") (class "Default")
      (node (ref "U6") (pin "21") (pinfunction "EP_21") (pintype "input"))
    )
    (net (code "25") (name "Net-(U4-B)") (class "Default")
      (node (ref "R2") (pin "1") (pinfunction "1_1") (pintype "input"))
      (node (ref "U4") (pin "1") (pinfunction "B_1") (pintype "input"))
    )
    (net (code "26") (name "Net-(U4-C)") (class "Default")
      (node (ref "R3") (pin "2") (pinfunction "2_2") (pintype "input"))
      (node (ref "R4") (pin "1") (pinfunction "1_1") (pintype "input"))
      (node (ref "U4") (pin "3") (pinfunction "C_3") (pintype "input"))
    )
    (net (code "27") (name "Net-(U5-B)") (class "Default")
      (node (ref "R4") (pin "2") (pinfunction "2_2") (pintype "input"))
      (node (ref "U5") (pin "1") (pinfunction "B_1") (pintype "input"))
    )
    (net (code "28") (name "Net-(U6-CCP)") (class "Default")
      (node (ref "C1") (pin "2") (pinfunction "2_2") (pintype "input"))
      (node (ref "U6") (pin "17") (pinfunction "CCP_17") (pintype "input"))
    )
    (net (code "29") (name "Net-(U6-D2#)") (class "Default")
      (node (ref "R7") (pin "2") (pinfunction "2_2") (pintype "input"))
      (node (ref "U6") (pin "13") (pinfunction "D2#_13") (pintype "input"))
    )
    (net (code "30") (name "Net-(U10-Xtal_Terminal_(Input))") (class "Default")
      (node (ref "C3") (pin "1") (pinfunction "1_1") (pintype "input"))
      (node (ref "U10") (pin "1") (pinfunction "Xtal_Terminal_(Input)_1") (pintype "input"))
      (node (ref "U11") (pin "8") (pinfunction "OSC1_8") (pintype "input"))
    )
    (net (code "31") (name "Net-(U10-Xtal_Terminal_(Output))") (class "Default")
      (node (ref "C2") (pin "1") (pinfunction "1_1") (pintype "input"))
      (node (ref "U10") (pin "3") (pinfunction "Xtal_Terminal_(Output)_3") (pintype "input"))
      (node (ref "U11") (pin "7") (pinfunction "OSC2_7") (pintype "input"))
    )
    (net (code "32") (name "Net-(U11-RXCAN)") (class "Default")
      (node (ref "U11") (pin "2") (pinfunction "RXCAN_2") (pintype "input"))
      (node (ref "U8") (pin "4") (pinfunction "RXD_4") (pintype "input"))
    )
    (net (code "33") (name "Net-(U11-TXCAN)") (class "Default")
      (node (ref "U11") (pin "1") (pinfunction "TXCAN_1") (pintype "input"))
      (node (ref "U8") (pin "1") (pinfunction "TXD_1") (pintype "input"))
    )
    (net (code "34") (name "RESET#") (class "Default")
      (node (ref "U1") (pin "28") (pinfunction "RESET_28") (pintype "input"))
      (node (ref "U11") (pin "17") (pinfunction "RESET#_17") (pintype "input"))
      (node (ref "U6") (pin "20") (pinfunction "EN_20") (pintype "input"))
    )
    (net (code "35") (name "TPS1") (class "Default")
      (node (ref "U1") (pin "19") (pinfunction "A0_19") (pintype "input"))
      (node (ref "U3") (pin "5") (pinfunction "5_5") (pintype "input"))
    )
    (net (code "36") (name "TPS2") (class "Default")
      (node (ref "U1") (pin "20") (pinfunction "A1_20") (pintype "input"))
      (node (ref "U3") (pin "6") (pinfunction "6_6") (pintype "input"))
    )
    (net (code "37") (name "WSPEED_IO") (class "Default")
      (node (ref "R5") (pin "1") (pinfunction "1_1") (pintype "input"))
      (node (ref "U1") (pin "5") (pinfunction "D2_5") (pintype "input"))
      (node (ref "U5") (pin "3") (pinfunction "C_3") (pintype "input"))
    )
    (net (code "38") (name "WSPEED_SENSOR") (class "Default")
      (node (ref "R1") (pin "2") (pinfunction "2_2") (pintype "input"))
      (node (ref "R2") (pin "2") (pinfunction "2_2") (pintype "input"))
      (node (ref "U2") (pin "6") (pinfunction "6_6") (pintype "input"))
    )
    (net (code "39") (name "unconnected-(U1-3V3-Pad17)") (class "Default")
      (node (ref "U1") (pin "17") (pinfunction "3V3_17") (pintype "input"))
    )
    (net (code "40") (name "unconnected-(U1-A6-Pad25)") (class "Default")
      (node (ref "U1") (pin "25") (pinfunction "A6_25") (pintype "input"))
    )
    (net (code "41") (name "unconnected-(U1-A7-Pad26)") (class "Default")
      (node (ref "U1") (pin "26") (pinfunction "A7_26") (pintype "input"))
    )
    (net (code "42") (name "unconnected-(U1-AREF-Pad18)") (class "Default")
      (node (ref "U1") (pin "18") (pinfunction "AREF_18") (pintype "input"))
    )
    (net (code "43") (name "unconnected-(U1-D0{slash}RX-Pad2)") (class "Default")
      (node (ref "U1") (pin "2") (pinfunction "D0/RX_2") (pintype "input"))
    )
    (net (code "44") (name "unconnected-(U1-D1{slash}TX-Pad1)") (class "Default")
      (node (ref "U1") (pin "1") (pinfunction "D1/TX_1") (pintype "input"))
    )
    (net (code "45") (name "unconnected-(U1-RESET-Pad3)") (class "Default")
      (node (ref "U1") (pin "3") (pinfunction "RESET_3") (pintype "input"))
    )
    (net (code "46") (name "unconnected-(U2-Pad10)") (class "Default")
      (node (ref "U2") (pin "10") (pinfunction "10_10") (pintype "input"))
    )
    (net (code "47") (name "unconnected-(U8-VREF-Pad5)") (class "Default")
      (node (ref "U8") (pin "5") (pinfunction "VREF_5") (pintype "input"))
    )
    (net (code "48") (name "unconnected-(U10-GND-Pad2)") (class "Default")
      (node (ref "U10") (pin "2") (pinfunction "GND_2") (pintype "input"))
    )
    (net (code "49") (name "unconnected-(U10-GND-Pad4)") (class "Default")
      (node (ref "U10") (pin "4") (pinfunction "GND_4") (pintype "input"))
    )
    (net (code "50") (name "unconnected-(U11-CLKOUT{slash}SOF-Pad3)") (class "Default")
      (node (ref "U11") (pin "3") (pinfunction "CLKOUT/SOF_3") (pintype "input"))
    )
    (net (code "51") (name "unconnected-(U11-RX0BF#-Pad11)") (class "Default")
      (node (ref "U11") (pin "11") (pinfunction "RX0BF#_11") (pintype "input"))
    )
    (net (code "52") (name "unconnected-(U11-RX1BF#-Pad10)") (class "Default")
      (node (ref "U11") (pin "10") (pinfunction "RX1BF#_10") (pintype "input"))
    )
    (net (code "53") (name "unconnected-(U11-TX0RTS#-Pad4)") (class "Default")
      (node (ref "U11") (pin "4") (pinfunction "TX0RTS#_4") (pintype "input"))
    )
    (net (code "54") (name "unconnected-(U11-TX1RTS#-Pad5)") (class "Default")
      (node (ref "U11") (pin "5") (pinfunction "TX1RTS#_5") (pintype "input"))
    )
    (net (code "55") (name "unconnected-(U11-TX2RTS#-Pad6)") (class "Default")
      (node (ref "U11") (pin "6") (pinfunction "TX2RTS#_6") (pintype "input"))
    )
  )
)
